# Rev05MergeRedux--LED_external.net
KiCad netlist of a schematic drawn in Altium Designer
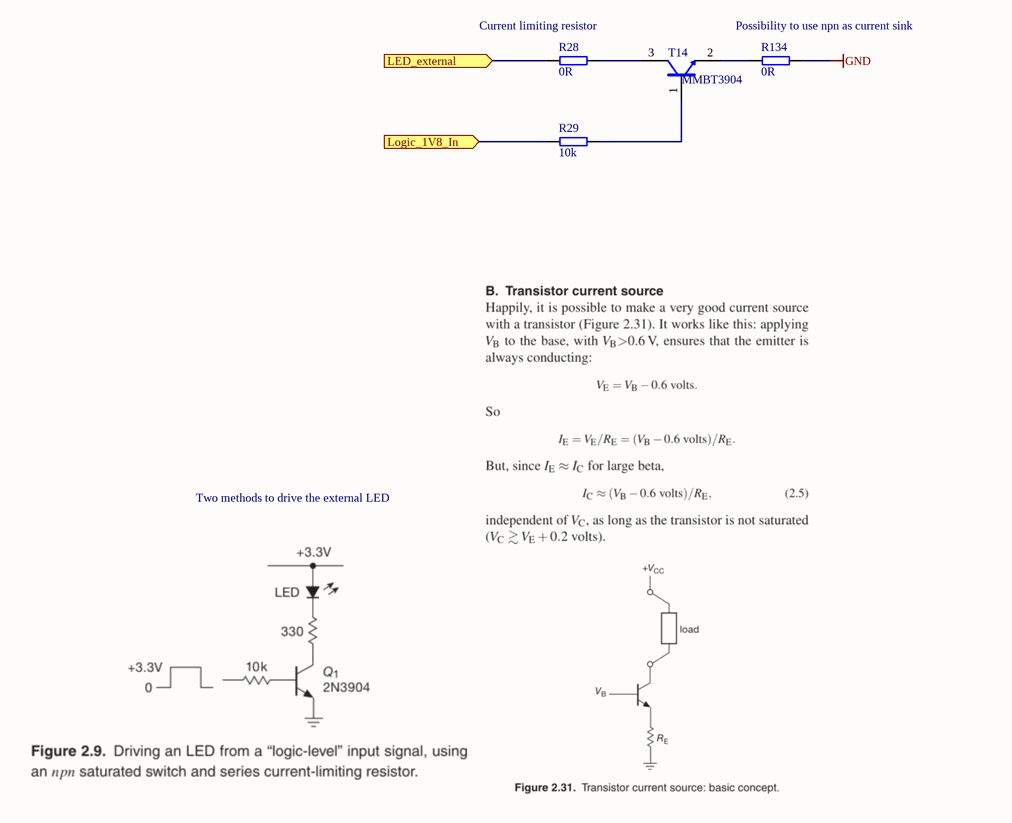
[diagram p0: Rev05MergeRedux--LED_external.SchDoc]

(export (version "E")
  (design (tool "Eeschema 10.0.6"))
  (components
    (comp (ref "R28")
      (value "0R")
      (footprint "R_0603_TE")
      (description "Generic resistor")
      (fields
        (field (name "TOLERANCE") "1 %")
        (field (name "MANUFACTURER PART NUMBER") "UZgen_R_0603_0R")
        (field (name "CREATED FROM") "UZgenTool")
      )
      (libsource (lib "user") (part "RES"))
    )
    (comp (ref "R29")
      (value "10k")
      (footprint "R_0603_TE")
      (description "Generic resistor")
      (fields
        (field (name "TOLERANCE") "1 %")
        (field (name "MANUFACTURER PART NUMBER") "UZgen_R_0603_10k")
        (field (name "CREATED FROM") "AGeiger")
      )
      (libsource (lib "user") (part "RES"))
    )
    (comp (ref "R134")
      (value "0R")
      (footprint "R_0603_TE")
      (description "Generic resistor")
      (fields
        (field (name "TOLERANCE") "1 %")
        (field (name "MANUFACTURER PART NUMBER") "UZgen_R_0603_0R")
        (field (name "CREATED FROM") "UZgenTool")
      )
      (libsource (lib "user") (part "RES"))
    )
    (comp (ref "T14")
      (value "MMBT3904")
      (footprint "SOT95P280X145-3N")
      (libsource (lib "TE") (part "NPN-SOT23"))
    )
  )
  (nets
    (net (code "1") (name "/LED_external") (class "Default")
      (node (ref "R28") (pin "2") (pinfunction "2_2") (pintype "passive"))
    )
    (net (code "2") (name "/Logic_1V8_In") (class "Default")
      (node (ref "R29") (pin "1") (pinfunction "1_1") (pintype "passive"))
    )
    (net (code "3") (name "GND") (class "Default")
      (node (ref "R134") (pin "1") (pinfunction "1_1") (pintype "passive"))
    )
    (net (code "4") (name "Net-(T14-BASIS)") (class "Default")
      (node (ref "R29") (pin "2") (pinfunction "2_2") (pintype "passive"))
      (node (ref "T14") (pin "1") (pinfunction "BASIS_1") (pintype "passive"))
    )
    (net (code "5") (name "Net-(T14-COLLECTOR)") (class "Default")
      (node (ref "R28") (pin "1") (pinfunction "1_1") (pintype "passive"))
      (node (ref "T14") (pin "3") (pinfunction "COLLECTOR_3") (pintype "passive"))
    )
    (net (code "6") (name "Net-(T14-EMITTER)") (class "Default")
      (node (ref "R134") (pin "2") (pinfunction "2_2") (pintype "passive"))
      (node (ref "T14") (pin "2") (pinfunction "EMITTER_2") (pintype "passive"))
    )
  )
)
